# PCB-CARDLOCK.net
KiCad netlist of a schematic drawn in EAGLE
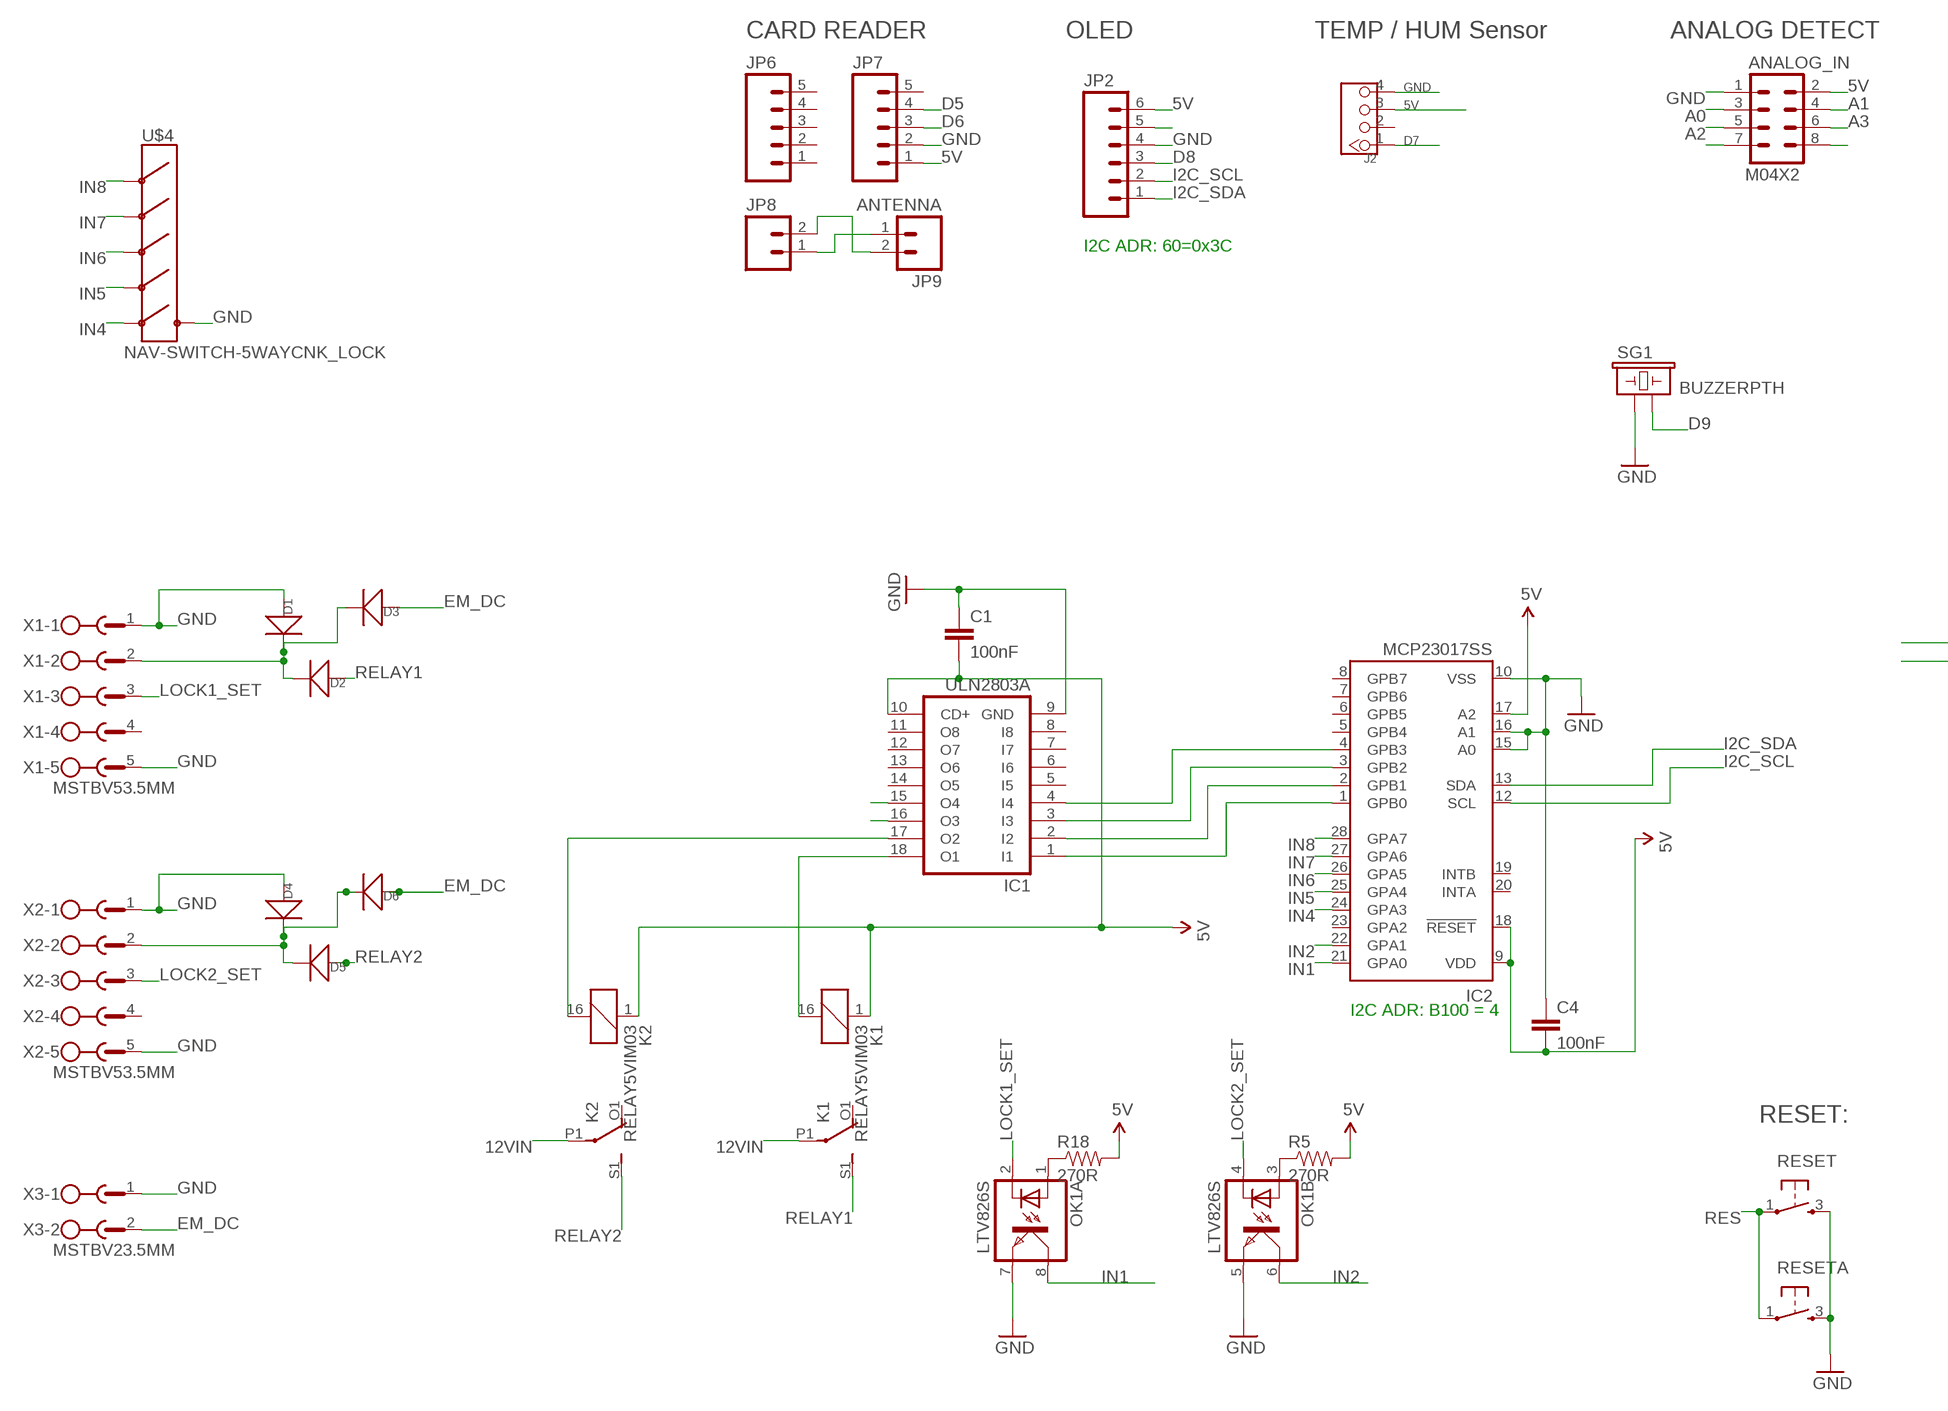
[diagram p0: schematic, sheet 1, part 1 of 2]
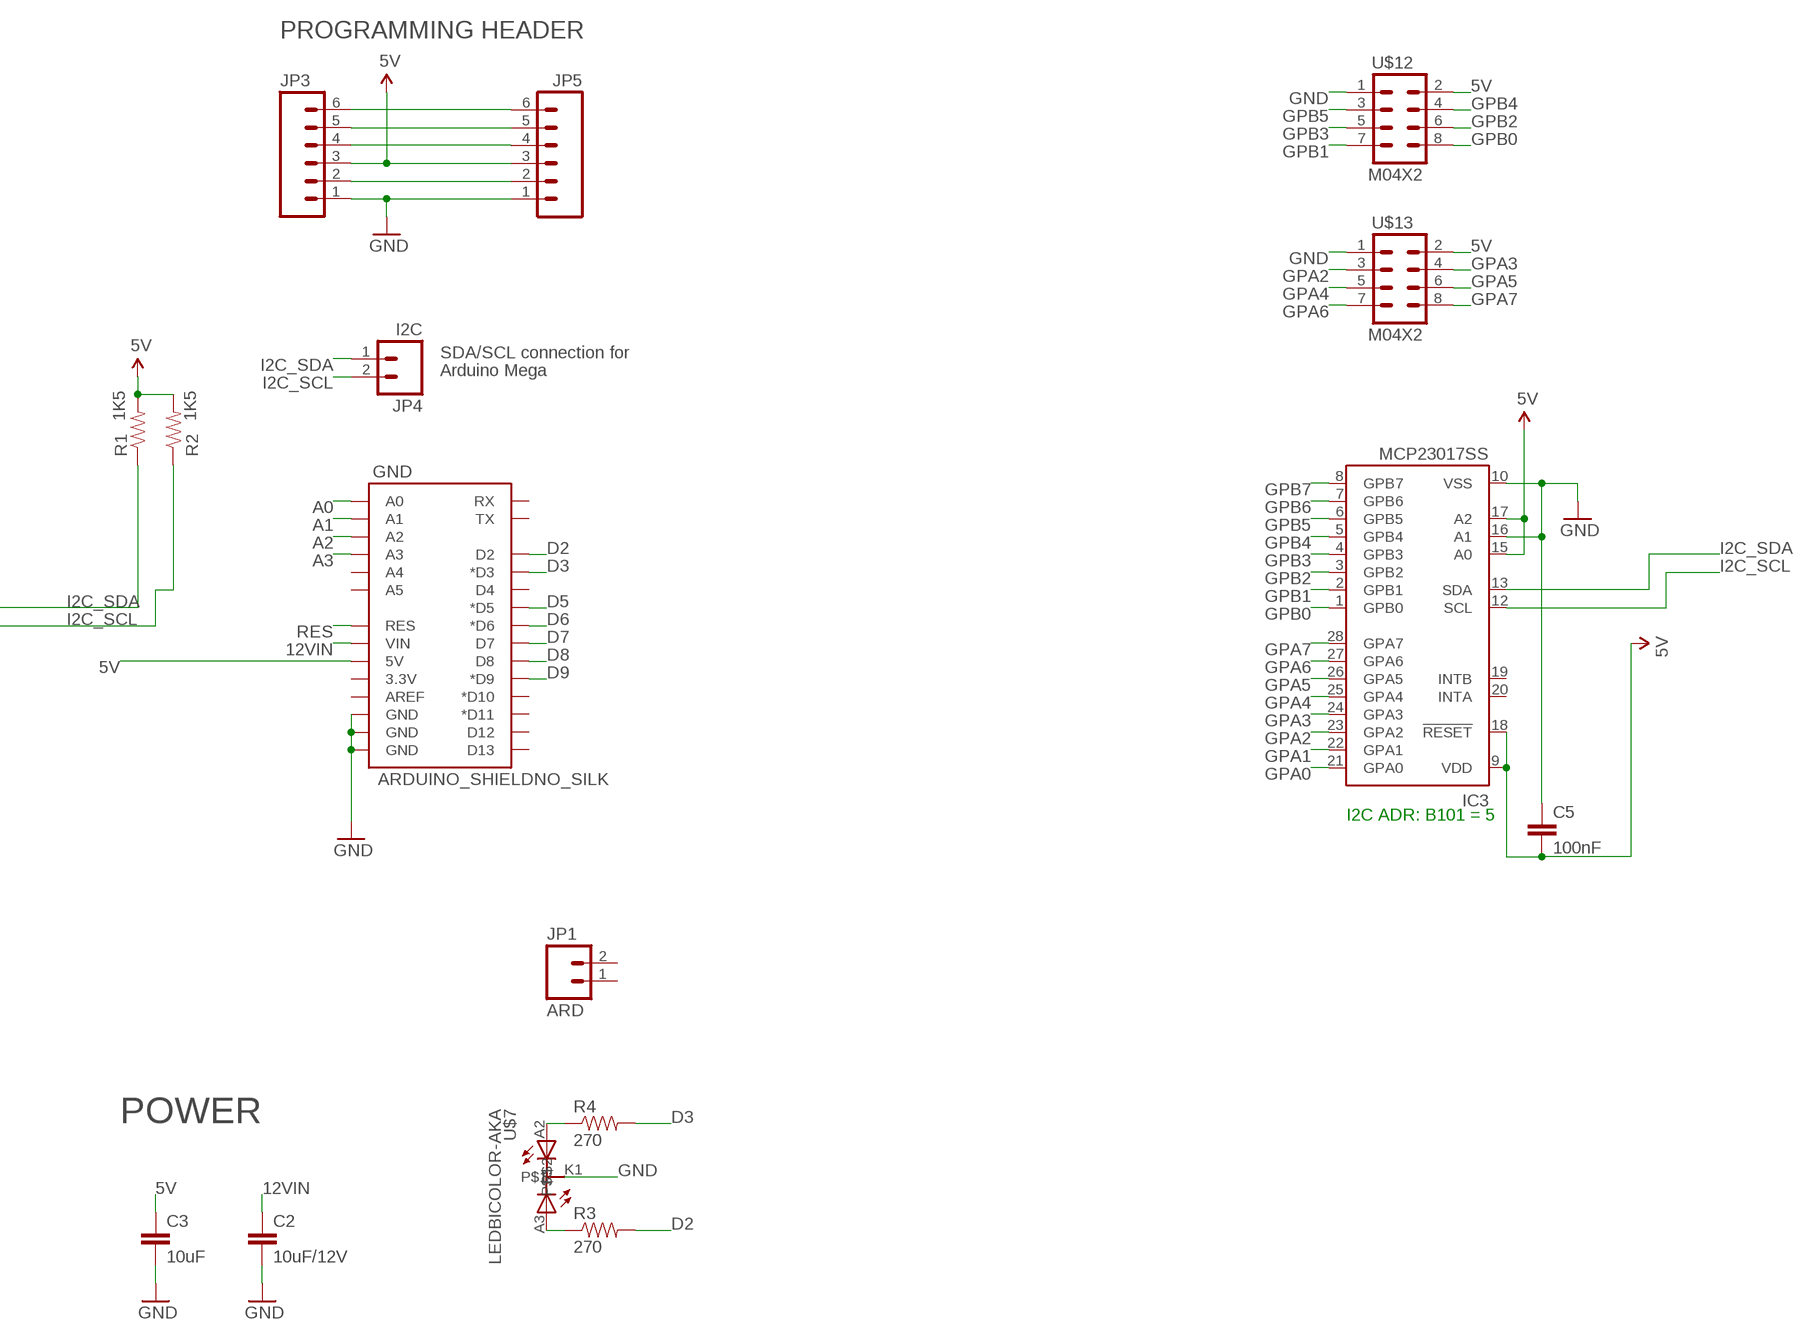
[diagram p1: schematic, sheet 1, part 2 of 2]

(export (version "E")
  (design (tool "Eeschema 10.0.6"))
  (components
    (comp (ref "ANALOG_IN")
      (value "M04X2")
      (footprint "eagle-import:2X4")
      (libsource (lib "eagle-import") (part "M04X2"))
    )
    (comp (ref "C1")
      (value "100nF")
      (footprint "eagle-import:0805")
      (libsource (lib "eagle-import") (part "CAP0805"))
    )
    (comp (ref "C2")
      (value "10uF/12V")
      (footprint "eagle-import:0805")
      (libsource (lib "eagle-import") (part "CAP0805"))
    )
    (comp (ref "C3")
      (value "10uF")
      (footprint "eagle-import:0805")
      (libsource (lib "eagle-import") (part "CAP0805"))
    )
    (comp (ref "C4")
      (value "100nF")
      (footprint "eagle-import:0603-CAP")
      (libsource (lib "eagle-import") (part "CAP0603-CAP"))
    )
    (comp (ref "C5")
      (value "100nF")
      (footprint "eagle-import:0603-CAP")
      (libsource (lib "eagle-import") (part "CAP0603-CAP"))
    )
    (comp (ref "D1")
      (value "D-SMA")
      (footprint "eagle-import:DO-214AC")
      (libsource (lib "eagle-import") (part "D-SMA"))
    )
    (comp (ref "D2")
      (value "D-SMA")
      (footprint "eagle-import:DO-214AC")
      (libsource (lib "eagle-import") (part "D-SMA"))
    )
    (comp (ref "D3")
      (value "D-SMA")
      (footprint "eagle-import:DO-214AC")
      (libsource (lib "eagle-import") (part "D-SMA"))
    )
    (comp (ref "D4")
      (value "D-SMA")
      (footprint "eagle-import:DO-214AC")
      (libsource (lib "eagle-import") (part "D-SMA"))
    )
    (comp (ref "D5")
      (value "D-SMA")
      (footprint "eagle-import:DO-214AC")
      (libsource (lib "eagle-import") (part "D-SMA"))
    )
    (comp (ref "D6")
      (value "D-SMA")
      (footprint "eagle-import:DO-214AC")
      (libsource (lib "eagle-import") (part "D-SMA"))
    )
    (comp (ref "GND")
      (value "ARDUINO_SHIELDNO_SILK")
      (footprint "eagle-import:DUEMILANOVE_VIAS")
      (libsource (lib "eagle-import") (part "ARDUINO_SHIELDNO_SILK"))
    )
    (comp (ref "IC1")
      (value "ULN2803A")
      (footprint "eagle-import:SO18W")
      (libsource (lib "eagle-import") (part "ULN2803ASO18W"))
    )
    (comp (ref "IC2")
      (value "MCP23017SS")
      (footprint "eagle-import:SSOP28")
      (fields (field (name "MF") "MICROCHIP") (field (name "MPN") "MCP23017-E/SS"))
      (libsource (lib "eagle-import") (part "MCP23017SS"))
    )
    (comp (ref "IC3")
      (value "MCP23017SS")
      (footprint "eagle-import:SSOP28")
      (fields (field (name "MF") "MICROCHIP") (field (name "MPN") "MCP23017-E/SS"))
      (libsource (lib "eagle-import") (part "MCP23017SS"))
    )
    (comp (ref "J2")
      (value "TWIG-4P-2.0-2.0")
      (footprint "eagle-import:4P-2.0")
      (libsource (lib "eagle-import") (part "TWIG-4P-2.0-2.0"))
    )
    (comp (ref "JP1")
      (value "ARD")
      (footprint "eagle-import:1X02")
      (libsource (lib "eagle-import") (part "M02PTH"))
    )
    (comp (ref "JP2")
      (value "M06POLAR")
      (footprint "eagle-import:MOLEX-1X6")
      (libsource (lib "eagle-import") (part "M06POLAR"))
    )
    (comp (ref "JP3")
      (value "M06POLAR")
      (footprint "eagle-import:MOLEX-1X6")
      (libsource (lib "eagle-import") (part "M06POLAR"))
    )
    (comp (ref "JP4")
      (value "I2C")
      (footprint "eagle-import:1X02")
      (libsource (lib "eagle-import") (part "M02PTH"))
    )
    (comp (ref "JP5")
      (value "M06POLAR")
      (footprint "eagle-import:MOLEX-1X6")
      (libsource (lib "eagle-import") (part "M06POLAR"))
    )
    (comp (ref "JP6")
      (value "M05PTH")
      (footprint "eagle-import:1X05")
      (libsource (lib "eagle-import") (part "M05PTH"))
    )
    (comp (ref "JP7")
      (value "M05PTH")
      (footprint "eagle-import:1X05")
      (libsource (lib "eagle-import") (part "M05PTH"))
    )
    (comp (ref "JP8")
      (value "M02PTH")
      (footprint "eagle-import:1X02")
      (libsource (lib "eagle-import") (part "M02PTH"))
    )
    (comp (ref "JP9")
      (value "ANTENNA")
      (footprint "eagle-import:1X02")
      (libsource (lib "eagle-import") (part "M02PTH"))
    )
    (comp (ref "K1")
      (value "RELAY5VIM03")
      (footprint "eagle-import:DS2Y")
      (libsource (lib "eagle-import") (part "RELAY5VIM03"))
    )
    (comp (ref "K2")
      (value "RELAY5VIM03")
      (footprint "eagle-import:DS2Y")
      (libsource (lib "eagle-import") (part "RELAY5VIM03"))
    )
    (comp (ref "OK1")
      (value "LTV826S")
      (footprint "eagle-import:DIL8-SMD")
      (libsource (lib "eagle-import") (part "LTV826S"))
    )
    (comp (ref "R1")
      (value "1K5")
      (footprint "eagle-import:0603-RES")
      (libsource (lib "eagle-import") (part "RESISTOR0603-RES"))
    )
    (comp (ref "R2")
      (value "1K5")
      (footprint "eagle-import:0603-RES")
      (libsource (lib "eagle-import") (part "RESISTOR0603-RES"))
    )
    (comp (ref "R3")
      (value "270")
      (footprint "eagle-import:0603-RES")
      (libsource (lib "eagle-import") (part "RESISTOR0603-RES"))
    )
    (comp (ref "R4")
      (value "270")
      (footprint "eagle-import:0603-RES")
      (libsource (lib "eagle-import") (part "RESISTOR0603-RES"))
    )
    (comp (ref "R5")
      (value "270R")
      (footprint "eagle-import:0603-RES")
      (libsource (lib "eagle-import") (part "RESISTOR0603-RES"))
    )
    (comp (ref "R18")
      (value "270R")
      (footprint "eagle-import:0603-RES")
      (libsource (lib "eagle-import") (part "RESISTOR0603-RES"))
    )
    (comp (ref "RESET")
      (value "TAC_SWITCH")
      (footprint "eagle-import:PUSHBUTTON")
      (libsource (lib "eagle-import") (part "TAC_SWITCH"))
    )
    (comp (ref "RESETA")
      (value "TAC_SWITCH")
      (footprint "eagle-import:PUSHBUTTON")
      (libsource (lib "eagle-import") (part "TAC_SWITCH"))
    )
    (comp (ref "SG1")
      (value "BUZZERPTH")
      (footprint "eagle-import:BUZZER-12MM")
      (libsource (lib "eagle-import") (part "BUZZERPTH"))
    )
    (comp (ref "U$4")
      (value "NAV-SWITCH-5WAYCNK_LOCK")
      (footprint "eagle-import:NAV-SWITCH-5WAY")
      (libsource (lib "eagle-import") (part "NAV-SWITCH-5WAYCNK_LOCK"))
    )
    (comp (ref "U$7")
      (value "LEDBICOLOR-AKA")
      (footprint "eagle-import:LED5MM-BICOLOR")
      (libsource (lib "eagle-import") (part "LEDBICOLOR-AKA"))
    )
    (comp (ref "U$12")
      (value "M04X2")
      (footprint "eagle-import:2X4")
      (libsource (lib "eagle-import") (part "M04X2"))
    )
    (comp (ref "U$13")
      (value "M04X2")
      (footprint "eagle-import:2X4")
      (libsource (lib "eagle-import") (part "M04X2"))
    )
    (comp (ref "X1")
      (value "MSTBV53.5MM")
      (footprint "eagle-import:MSTBV5-3.5")
      (libsource (lib "eagle-import") (part "MSTBV53.5MM"))
    )
    (comp (ref "X2")
      (value "MSTBV53.5MM")
      (footprint "eagle-import:MSTBV5-3.5")
      (libsource (lib "eagle-import") (part "MSTBV53.5MM"))
    )
    (comp (ref "X3")
      (value "MSTBV23.5MM")
      (footprint "eagle-import:MSTBV2-3.5")
      (libsource (lib "eagle-import") (part "MSTBV23.5MM"))
    )
  )
  (nets
    (net (code "1") (name "5V") (class "Default")
      (node (ref "ANALOG_IN") (pin "2") (pinfunction "2_2") (pintype "passive"))
      (node (ref "C1") (pin "2") (pinfunction "2_2") (pintype "passive"))
      (node (ref "C3") (pin "1") (pinfunction "1_1") (pintype "passive"))
      (node (ref "C4") (pin "2") (pinfunction "2_2") (pintype "passive"))
      (node (ref "C5") (pin "2") (pinfunction "2_2") (pintype "passive"))
      (node (ref "GND") (pin "5V") (pinfunction "5V_5V") (pintype "bidirectional"))
      (node (ref "IC1") (pin "10") (pinfunction "CD+_10") (pintype "passive"))
      (node (ref "IC2") (pin "17") (pinfunction "A2_17") (pintype "input"))
      (node (ref "IC2") (pin "18") (pinfunction "~{RESET}_18") (pintype "input"))
      (node (ref "IC2") (pin "9") (pinfunction "VDD_9") (pintype "power_in"))
      (node (ref "IC3") (pin "15") (pinfunction "A0_15") (pintype "input"))
      (node (ref "IC3") (pin "17") (pinfunction "A2_17") (pintype "input"))
      (node (ref "IC3") (pin "18") (pinfunction "~{RESET}_18") (pintype "input"))
      (node (ref "IC3") (pin "9") (pinfunction "VDD_9") (pintype "power_in"))
      (node (ref "J2") (pin "3") (pinfunction "3_3") (pintype "bidirectional"))
      (node (ref "JP2") (pin "6") (pinfunction "6_6") (pintype "passive"))
      (node (ref "JP3") (pin "3") (pinfunction "3_3") (pintype "passive"))
      (node (ref "JP5") (pin "3") (pinfunction "3_3") (pintype "passive"))
      (node (ref "JP7") (pin "1") (pinfunction "1_1") (pintype "passive"))
      (node (ref "K1") (pin "1") (pinfunction "1_1") (pintype "passive"))
      (node (ref "K2") (pin "1") (pinfunction "1_1") (pintype "passive"))
      (node (ref "R1") (pin "2") (pinfunction "2_2") (pintype "passive"))
      (node (ref "R18") (pin "2") (pinfunction "2_2") (pintype "passive"))
      (node (ref "R2") (pin "2") (pinfunction "2_2") (pintype "passive"))
      (node (ref "R5") (pin "2") (pinfunction "2_2") (pintype "passive"))
      (node (ref "U$12") (pin "2") (pinfunction "2_2") (pintype "passive"))
      (node (ref "U$13") (pin "2") (pinfunction "2_2") (pintype "passive"))
    )
    (net (code "2") (name "12VIN") (class "Default")
      (node (ref "C2") (pin "1") (pinfunction "1_1") (pintype "passive"))
      (node (ref "GND") (pin "VIN") (pinfunction "VIN_VIN") (pintype "bidirectional"))
      (node (ref "K1") (pin "P1") (pinfunction "P_P1") (pintype "passive"))
      (node (ref "K2") (pin "P1") (pinfunction "P_P1") (pintype "passive"))
    )
    (net (code "3") (name "A0") (class "Default")
      (node (ref "ANALOG_IN") (pin "3") (pinfunction "3_3") (pintype "passive"))
      (node (ref "GND") (pin "A0") (pinfunction "A0_A0") (pintype "bidirectional"))
    )
    (net (code "4") (name "A1") (class "Default")
      (node (ref "ANALOG_IN") (pin "4") (pinfunction "4_4") (pintype "passive"))
      (node (ref "GND") (pin "A1") (pinfunction "A1_A1") (pintype "bidirectional"))
    )
    (net (code "5") (name "A2") (class "Default")
      (node (ref "ANALOG_IN") (pin "5") (pinfunction "5_5") (pintype "passive"))
      (node (ref "GND") (pin "A2") (pinfunction "A2_A2") (pintype "bidirectional"))
    )
    (net (code "6") (name "A3") (class "Default")
      (node (ref "ANALOG_IN") (pin "6") (pinfunction "6_6") (pintype "passive"))
      (node (ref "GND") (pin "A3") (pinfunction "A3_A3") (pintype "bidirectional"))
    )
    (net (code "7") (name "D2") (class "Default")
      (node (ref "GND") (pin "D2") (pinfunction "D2_D2") (pintype "bidirectional"))
      (node (ref "R3") (pin "2") (pinfunction "2_2") (pintype "passive"))
    )
    (net (code "8") (name "D3") (class "Default")
      (node (ref "GND") (pin "D3") (pinfunction "*D3_D3") (pintype "bidirectional"))
      (node (ref "R4") (pin "2") (pinfunction "2_2") (pintype "passive"))
    )
    (net (code "9") (name "D5") (class "Default")
      (node (ref "GND") (pin "D5") (pinfunction "*D5_D5") (pintype "bidirectional"))
      (node (ref "JP7") (pin "4") (pinfunction "4_4") (pintype "passive"))
    )
    (net (code "10") (name "D6") (class "Default")
      (node (ref "GND") (pin "D6") (pinfunction "*D6_D6") (pintype "bidirectional"))
      (node (ref "JP7") (pin "3") (pinfunction "3_3") (pintype "passive"))
    )
    (net (code "11") (name "D7") (class "Default")
      (node (ref "GND") (pin "D7") (pinfunction "D7_D7") (pintype "bidirectional"))
      (node (ref "J2") (pin "1") (pinfunction "1_1") (pintype "bidirectional"))
    )
    (net (code "12") (name "D8") (class "Default")
      (node (ref "GND") (pin "D8") (pinfunction "D8_D8") (pintype "bidirectional"))
      (node (ref "JP2") (pin "3") (pinfunction "3_3") (pintype "passive"))
    )
    (net (code "13") (name "D9") (class "Default")
      (node (ref "GND") (pin "D9") (pinfunction "*D9_D9") (pintype "bidirectional"))
      (node (ref "SG1") (pin "-") (pinfunction "2_-") (pintype "passive"))
    )
    (net (code "14") (name "EM_DC") (class "Default")
      (node (ref "D3") (pin "1") (pinfunction "+_1") (pintype "passive"))
      (node (ref "D6") (pin "1") (pinfunction "+_1") (pintype "passive"))
      (node (ref "X3") (pin "2") (pinfunction "1_2") (pintype "passive"))
    )
    (net (code "15") (name "GND") (class "Default")
      (node (ref "ANALOG_IN") (pin "1") (pinfunction "1_1") (pintype "passive"))
      (node (ref "C1") (pin "1") (pinfunction "1_1") (pintype "passive"))
      (node (ref "C2") (pin "2") (pinfunction "2_2") (pintype "passive"))
      (node (ref "C3") (pin "2") (pinfunction "2_2") (pintype "passive"))
      (node (ref "C4") (pin "1") (pinfunction "1_1") (pintype "passive"))
      (node (ref "C5") (pin "1") (pinfunction "1_1") (pintype "passive"))
      (node (ref "D1") (pin "1") (pinfunction "+_1") (pintype "passive"))
      (node (ref "D4") (pin "1") (pinfunction "+_1") (pintype "passive"))
      (node (ref "GND") (pin "GND@0") (pinfunction "GND_GND@0") (pintype "bidirectional"))
      (node (ref "GND") (pin "GND@1") (pinfunction "GND_GND@1") (pintype "bidirectional"))
      (node (ref "GND") (pin "GND@2") (pinfunction "GND_GND@2") (pintype "bidirectional"))
      (node (ref "IC1") (pin "9") (pinfunction "GND_9") (pintype "power_in"))
      (node (ref "IC2") (pin "10") (pinfunction "VSS_10") (pintype "power_in"))
      (node (ref "IC2") (pin "15") (pinfunction "A0_15") (pintype "input"))
      (node (ref "IC2") (pin "16") (pinfunction "A1_16") (pintype "input"))
      (node (ref "IC3") (pin "10") (pinfunction "VSS_10") (pintype "power_in"))
      (node (ref "IC3") (pin "16") (pinfunction "A1_16") (pintype "input"))
      (node (ref "J2") (pin "4") (pinfunction "4_4") (pintype "bidirectional"))
      (node (ref "JP2") (pin "4") (pinfunction "4_4") (pintype "passive"))
      (node (ref "JP3") (pin "1") (pinfunction "1_1") (pintype "passive"))
      (node (ref "JP5") (pin "1") (pinfunction "1_1") (pintype "passive"))
      (node (ref "JP7") (pin "2") (pinfunction "2_2") (pintype "passive"))
      (node (ref "OK1") (pin "5") (pinfunction "EMIT_5") (pintype "passive"))
      (node (ref "OK1") (pin "7") (pinfunction "EMIT_7") (pintype "passive"))
      (node (ref "RESET") (pin "3") (pinfunction "3_3") (pintype "passive"))
      (node (ref "RESETA") (pin "3") (pinfunction "3_3") (pintype "passive"))
      (node (ref "SG1") (pin "+") (pinfunction "1_+") (pintype "passive"))
      (node (ref "U$12") (pin "1") (pinfunction "1_1") (pintype "passive"))
      (node (ref "U$13") (pin "1") (pinfunction "1_1") (pintype "passive"))
      (node (ref "U$4") (pin "PIN4") (pinfunction "COMMON_PIN4") (pintype "bidirectional"))
      (node (ref "U$7") (pin "K1") (pinfunction "P$1_K1") (pintype "bidirectional"))
      (node (ref "X1") (pin "1") (pinfunction "1_1") (pintype "passive"))
      (node (ref "X1") (pin "5") (pinfunction "1_5") (pintype "passive"))
      (node (ref "X2") (pin "1") (pinfunction "1_1") (pintype "passive"))
      (node (ref "X2") (pin "5") (pinfunction "1_5") (pintype "passive"))
      (node (ref "X3") (pin "1") (pinfunction "1_1") (pintype "passive"))
    )
    (net (code "16") (name "GPA0") (class "Default")
      (node (ref "IC3") (pin "21") (pinfunction "GPA0_21") (pintype "bidirectional"))
    )
    (net (code "17") (name "GPA1") (class "Default")
      (node (ref "IC3") (pin "22") (pinfunction "GPA1_22") (pintype "bidirectional"))
    )
    (net (code "18") (name "GPA2") (class "Default")
      (node (ref "IC3") (pin "23") (pinfunction "GPA2_23") (pintype "bidirectional"))
      (node (ref "U$13") (pin "3") (pinfunction "3_3") (pintype "passive"))
    )
    (net (code "19") (name "GPA3") (class "Default")
      (node (ref "IC3") (pin "24") (pinfunction "GPA3_24") (pintype "bidirectional"))
      (node (ref "U$13") (pin "4") (pinfunction "4_4") (pintype "passive"))
    )
    (net (code "20") (name "GPA4") (class "Default")
      (node (ref "IC3") (pin "25") (pinfunction "GPA4_25") (pintype "bidirectional"))
      (node (ref "U$13") (pin "5") (pinfunction "5_5") (pintype "passive"))
    )
    (net (code "21") (name "GPA5") (class "Default")
      (node (ref "IC3") (pin "26") (pinfunction "GPA5_26") (pintype "bidirectional"))
      (node (ref "U$13") (pin "6") (pinfunction "6_6") (pintype "passive"))
    )
    (net (code "22") (name "GPA6") (class "Default")
      (node (ref "IC3") (pin "27") (pinfunction "GPA6_27") (pintype "bidirectional"))
      (node (ref "U$13") (pin "7") (pinfunction "7_7") (pintype "passive"))
    )
    (net (code "23") (name "GPA7") (class "Default")
      (node (ref "IC3") (pin "28") (pinfunction "GPA7_28") (pintype "bidirectional"))
      (node (ref "U$13") (pin "8") (pinfunction "8_8") (pintype "passive"))
    )
    (net (code "24") (name "GPB0") (class "Default")
      (node (ref "IC3") (pin "1") (pinfunction "GPB0_1") (pintype "bidirectional"))
      (node (ref "U$12") (pin "8") (pinfunction "8_8") (pintype "passive"))
    )
    (net (code "25") (name "GPB1") (class "Default")
      (node (ref "IC3") (pin "2") (pinfunction "GPB1_2") (pintype "bidirectional"))
      (node (ref "U$12") (pin "7") (pinfunction "7_7") (pintype "passive"))
    )
    (net (code "26") (name "GPB2") (class "Default")
      (node (ref "IC3") (pin "3") (pinfunction "GPB2_3") (pintype "bidirectional"))
      (node (ref "U$12") (pin "6") (pinfunction "6_6") (pintype "passive"))
    )
    (net (code "27") (name "GPB3") (class "Default")
      (node (ref "IC3") (pin "4") (pinfunction "GPB3_4") (pintype "bidirectional"))
      (node (ref "U$12") (pin "5") (pinfunction "5_5") (pintype "passive"))
    )
    (net (code "28") (name "GPB4") (class "Default")
      (node (ref "IC3") (pin "5") (pinfunction "GPB4_5") (pintype "bidirectional"))
      (node (ref "U$12") (pin "4") (pinfunction "4_4") (pintype "passive"))
    )
    (net (code "29") (name "GPB5") (class "Default")
      (node (ref "IC3") (pin "6") (pinfunction "GPB5_6") (pintype "bidirectional"))
      (node (ref "U$12") (pin "3") (pinfunction "3_3") (pintype "passive"))
    )
    (net (code "30") (name "GPB6") (class "Default")
      (node (ref "IC3") (pin "7") (pinfunction "GPB6_7") (pintype "bidirectional"))
    )
    (net (code "31") (name "GPB7") (class "Default")
      (node (ref "IC3") (pin "8") (pinfunction "GPB7_8") (pintype "bidirectional"))
    )
    (net (code "32") (name "I2C_SCL") (class "Default")
      (node (ref "IC2") (pin "12") (pinfunction "SCL_12") (pintype "input"))
      (node (ref "IC3") (pin "12") (pinfunction "SCL_12") (pintype "input"))
      (node (ref "JP2") (pin "2") (pinfunction "2_2") (pintype "passive"))
      (node (ref "JP4") (pin "2") (pinfunction "2_2") (pintype "passive"))
      (node (ref "R2") (pin "1") (pinfunction "1_1") (pintype "passive"))
    )
    (net (code "33") (name "I2C_SDA") (class "Default")
      (node (ref "IC2") (pin "13") (pinfunction "SDA_13") (pintype "bidirectional"))
      (node (ref "IC3") (pin "13") (pinfunction "SDA_13") (pintype "bidirectional"))
      (node (ref "JP2") (pin "1") (pinfunction "1_1") (pintype "passive"))
      (node (ref "JP4") (pin "1") (pinfunction "1_1") (pintype "passive"))
      (node (ref "R1") (pin "1") (pinfunction "1_1") (pintype "passive"))
    )
    (net (code "34") (name "IN1") (class "Default")
      (node (ref "IC2") (pin "21") (pinfunction "GPA0_21") (pintype "bidirectional"))
      (node (ref "OK1") (pin "8") (pinfunction "COL_8") (pintype "passive"))
    )
    (net (code "35") (name "IN2") (class "Default")
      (node (ref "IC2") (pin "22") (pinfunction "GPA1_22") (pintype "bidirectional"))
      (node (ref "OK1") (pin "6") (pinfunction "COL_6") (pintype "passive"))
    )
    (net (code "36") (name "IN4") (class "Default")
      (node (ref "IC2") (pin "24") (pinfunction "GPA3_24") (pintype "bidirectional"))
      (node (ref "U$4") (pin "PIN6") (pinfunction "PUSH_PIN6") (pintype "bidirectional"))
    )
    (net (code "37") (name "IN5") (class "Default")
      (node (ref "IC2") (pin "25") (pinfunction "GPA4_25") (pintype "bidirectional"))
      (node (ref "U$4") (pin "PIN5") (pinfunction "RIGHT_PIN5") (pintype "bidirectional"))
    )
    (net (code "38") (name "IN6") (class "Default")
      (node (ref "IC2") (pin "26") (pinfunction "GPA5_26") (pintype "bidirectional"))
      (node (ref "U$4") (pin "PIN2") (pinfunction "LEFT_PIN2") (pintype "bidirectional"))
    )
    (net (code "39") (name "IN7") (class "Default")
      (node (ref "IC2") (pin "27") (pinfunction "GPA6_27") (pintype "bidirectional"))
      (node (ref "U$4") (pin "PIN3") (pinfunction "DWN_PIN3") (pintype "bidirectional"))
    )
    (net (code "40") (name "IN8") (class "Default")
      (node (ref "IC2") (pin "28") (pinfunction "GPA7_28") (pintype "bidirectional"))
      (node (ref "U$4") (pin "PIN1") (pinfunction "UP_PIN1") (pintype "bidirectional"))
    )
    (net (code "41") (name "LOCK1_SET") (class "Default")
      (node (ref "OK1") (pin "2") (pinfunction "C_2") (pintype "passive"))
      (node (ref "X1") (pin "3") (pinfunction "1_3") (pintype "passive"))
    )
    (net (code "42") (name "LOCK2_SET") (class "Default")
      (node (ref "OK1") (pin "4") (pinfunction "C_4") (pintype "passive"))
      (node (ref "X2") (pin "3") (pinfunction "1_3") (pintype "passive"))
    )
    (net (code "43") (name "Net-(D1--)") (class "Default")
      (node (ref "D1") (pin "2") (pinfunction "-_2") (pintype "passive"))
      (node (ref "D2") (pin "2") (pinfunction "-_2") (pintype "passive"))
      (node (ref "D3") (pin "2") (pinfunction "-_2") (pintype "passive"))
      (node (ref "X1") (pin "2") (pinfunction "1_2") (pintype "passive"))
    )
    (net (code "44") (name "Net-(D4--)") (class "Default")
      (node (ref "D4") (pin "2") (pinfunction "-_2") (pintype "passive"))
      (node (ref "D5") (pin "2") (pinfunction "-_2") (pintype "passive"))
      (node (ref "D6") (pin "2") (pinfunction "-_2") (pintype "passive"))
      (node (ref "X2") (pin "2") (pinfunction "1_2") (pintype "passive"))
    )
    (net (code "45") (name "Net-(IC1-I1)") (class "Default")
      (node (ref "IC1") (pin "1") (pinfunction "I1_1") (pintype "input"))
      (node (ref "IC2") (pin "1") (pinfunction "GPB0_1") (pintype "bidirectional"))
    )
    (net (code "46") (name "Net-(IC1-I2)") (class "Default")
      (node (ref "IC1") (pin "2") (pinfunction "I2_2") (pintype "input"))
      (node (ref "IC2") (pin "2") (pinfunction "GPB1_2") (pintype "bidirectional"))
    )
    (net (code "47") (name "Net-(IC1-I3)") (class "Default")
      (node (ref "IC1") (pin "3") (pinfunction "I3_3") (pintype "input"))
      (node (ref "IC2") (pin "3") (pinfunction "GPB2_3") (pintype "bidirectional"))
    )
    (net (code "48") (name "Net-(IC1-I4)") (class "Default")
      (node (ref "IC1") (pin "4") (pinfunction "I4_4") (pintype "input"))
      (node (ref "IC2") (pin "4") (pinfunction "GPB3_4") (pintype "bidirectional"))
    )
    (net (code "49") (name "Net-(IC1-O1)") (class "Default")
      (node (ref "IC1") (pin "18") (pinfunction "O1_18") (pintype "open_collector"))
      (node (ref "K1") (pin "16") (pinfunction "2_16") (pintype "passive"))
    )
    (net (code "50") (name "Net-(IC1-O2)") (class "Default")
      (node (ref "IC1") (pin "17") (pinfunction "O2_17") (pintype "open_collector"))
      (node (ref "K2") (pin "16") (pinfunction "2_16") (pintype "passive"))
    )
    (net (code "51") (name "Net-(JP3-Pad2)") (class "Default")
      (node (ref "JP3") (pin "2") (pinfunction "2_2") (pintype "passive"))
      (node (ref "JP5") (pin "2") (pinfunction "2_2") (pintype "passive"))
    )
    (net (code "52") (name "Net-(JP3-Pad4)") (class "Default")
      (node (ref "JP3") (pin "4") (pinfunction "4_4") (pintype "passive"))
      (node (ref "JP5") (pin "4") (pinfunction "4_4") (pintype "passive"))
    )
    (net (code "53") (name "Net-(JP3-Pad5)") (class "Default")
      (node (ref "JP3") (pin "5") (pinfunction "5_5") (pintype "passive"))
      (node (ref "JP5") (pin "5") (pinfunction "5_5") (pintype "passive"))
    )
    (net (code "54") (name "Net-(JP3-Pad6)") (class "Default")
      (node (ref "JP3") (pin "6") (pinfunction "6_6") (pintype "passive"))
      (node (ref "JP5") (pin "6") (pinfunction "6_6") (pintype "passive"))
    )
    (net (code "55") (name "Net-(JP8-Pad1)") (class "Default")
      (node (ref "JP8") (pin "1") (pinfunction "1_1") (pintype "passive"))
      (node (ref "JP9") (pin "1") (pinfunction "1_1") (pintype "passive"))
    )
    (net (code "56") (name "Net-(JP8-Pad2)") (class "Default")
      (node (ref "JP8") (pin "2") (pinfunction "2_2") (pintype "passive"))
      (node (ref "JP9") (pin "2") (pinfunction "2_2") (pintype "passive"))
    )
    (net (code "57") (name "Net-(OK1A-A)") (class "Default")
      (node (ref "OK1") (pin "1") (pinfunction "A_1") (pintype "passive"))
      (node (ref "R18") (pin "1") (pinfunction "1_1") (pintype "passive"))
    )
    (net (code "58") (name "Net-(OK1B-A)") (class "Default")
      (node (ref "OK1") (pin "3") (pinfunction "A_3") (pintype "passive"))
      (node (ref "R5") (pin "1") (pinfunction "1_1") (pintype "passive"))
    )
    (net (code "59") (name "Net-(U$7-P$2)") (class "Default")
      (node (ref "R4") (pin "1") (pinfunction "1_1") (pintype "passive"))
      (node (ref "U$7") (pin "A2") (pinfunction "P$2_A2") (pintype "bidirectional"))
    )
    (net (code "60") (name "Net-(U$7-P$3)") (class "Default")
      (node (ref "R3") (pin "1") (pinfunction "1_1") (pintype "passive"))
      (node (ref "U$7") (pin "A3") (pinfunction "P$3_A3") (pintype "bidirectional"))
    )
    (net (code "61") (name "RELAY1") (class "Default")
      (node (ref "D2") (pin "1") (pinfunction "+_1") (pintype "passive"))
      (node (ref "K1") (pin "S1") (pinfunction "S_S1") (pintype "passive"))
    )
    (net (code "62") (name "RELAY2") (class "Default")
      (node (ref "D5") (pin "1") (pinfunction "+_1") (pintype "passive"))
      (node (ref "K2") (pin "S1") (pinfunction "S_S1") (pintype "passive"))
    )
    (net (code "63") (name "RES") (class "Default")
      (node (ref "GND") (pin "RES") (pinfunction "RES_RES") (pintype "bidirectional"))
      (node (ref "RESET") (pin "1") (pinfunction "1_1") (pintype "passive"))
      (node (ref "RESETA") (pin "1") (pinfunction "1_1") (pintype "passive"))
    )
    (net (code "64") (name "unconnected-(ANALOG_IN-Pad7)") (class "Default")
      (node (ref "ANALOG_IN") (pin "7") (pinfunction "7_7") (pintype "passive"))
    )
    (net (code "65") (name "unconnected-(ANALOG_IN-Pad8)") (class "Default")
      (node (ref "ANALOG_IN") (pin "8") (pinfunction "8_8") (pintype "passive"))
    )
    (net (code "66") (name "unconnected-(GND-*D10-PadD10)") (class "Default")
      (node (ref "GND") (pin "D10") (pinfunction "*D10_D10") (pintype "bidirectional"))
    )
    (net (code "67") (name "unconnected-(GND-*D11-PadD11)") (class "Default")
      (node (ref "GND") (pin "D11") (pinfunction "*D11_D11") (pintype "bidirectional"))
    )
    (net (code "68") (name "unconnected-(GND-Pad3.3V)") (class "Default")
      (node (ref "GND") (pin "3.3V") (pinfunction "3.3V_3.3V") (pintype "bidirectional"))
    )
    (net (code "69") (name "unconnected-(GND-PadA4)") (class "Default")
      (node (ref "GND") (pin "A4") (pinfunction "A4_A4") (pintype "bidirectional"))
    )
    (net (code "70") (name "unconnected-(GND-PadA5)") (class "Default")
      (node (ref "GND") (pin "A5") (pinfunction "A5_A5") (pintype "bidirectional"))
    )
    (net (code "71") (name "unconnected-(GND-PadAREF)") (class "Default")
      (node (ref "GND") (pin "AREF") (pinfunction "AREF_AREF") (pintype "bidirectional"))
    )
    (net (code "72") (name "unconnected-(GND-PadD4)") (class "Default")
      (node (ref "GND") (pin "D4") (pinfunction "D4_D4") (pintype "bidirectional"))
    )
    (net (code "73") (name "unconnected-(GND-PadD12)") (class "Default")
      (node (ref "GND") (pin "D12") (pinfunction "D12_D12") (pintype "bidirectional"))
    )
    (net (code "74") (name "unconnected-(GND-PadD13)") (class "Default")
      (node (ref "GND") (pin "D13") (pinfunction "D13_D13") (pintype "bidirectional"))
    )
    (net (code "75") (name "unconnected-(GND-PadRX)") (class "Default")
      (node (ref "GND") (pin "RX") (pinfunction "RX_RX") (pintype "bidirectional"))
    )
    (net (code "76") (name "unconnected-(GND-PadTX)") (class "Default")
      (node (ref "GND") (pin "TX") (pinfunction "TX_TX") (pintype "bidirectional"))
    )
    (net (code "77") (name "unconnected-(IC1-I5-Pad5)") (class "Default")
      (node (ref "IC1") (pin "5") (pinfunction "I5_5") (pintype "input"))
    )
    (net (code "78") (name "unconnected-(IC1-I6-Pad6)") (class "Default")
      (node (ref "IC1") (pin "6") (pinfunction "I6_6") (pintype "input"))
    )
    (net (code "79") (name "unconnected-(IC1-I7-Pad7)") (class "Default")
      (node (ref "IC1") (pin "7") (pinfunction "I7_7") (pintype "input"))
    )
    (net (code "80") (name "unconnected-(IC1-I8-Pad8)") (class "Default")
      (node (ref "IC1") (pin "8") (pinfunction "I8_8") (pintype "input"))
    )
    (net (code "81") (name "unconnected-(IC1-O3-Pad16)") (class "Default")
      (node (ref "IC1") (pin "16") (pinfunction "O3_16") (pintype "open_collector"))
    )
    (net (code "82") (name "unconnected-(IC1-O4-Pad15)") (class "Default")
      (node (ref "IC1") (pin "15") (pinfunction "O4_15") (pintype "open_collector"))
    )
    (net (code "83") (name "unconnected-(IC1-O5-Pad14)") (class "Default")
      (node (ref "IC1") (pin "14") (pinfunction "O5_14") (pintype "open_collector"))
    )
    (net (code "84") (name "unconnected-(IC1-O6-Pad13)") (class "Default")
      (node (ref "IC1") (pin "13") (pinfunction "O6_13") (pintype "open_collector"))
    )
    (net (code "85") (name "unconnected-(IC1-O7-Pad12)") (class "Default")
      (node (ref "IC1") (pin "12") (pinfunction "O7_12") (pintype "open_collector"))
    )
    (net (code "86") (name "unconnected-(IC1-O8-Pad11)") (class "Default")
      (node (ref "IC1") (pin "11") (pinfunction "O8_11") (pintype "open_collector"))
    )
    (net (code "87") (name "unconnected-(IC2-GPA2-Pad23)") (class "Default")
      (node (ref "IC2") (pin "23") (pinfunction "GPA2_23") (pintype "bidirectional"))
    )
    (net (code "88") (name "unconnected-(IC2-GPB4-Pad5)") (class "Default")
      (node (ref "IC2") (pin "5") (pinfunction "GPB4_5") (pintype "bidirectional"))
    )
    (net (code "89") (name "unconnected-(IC2-GPB5-Pad6)") (class "Default")
      (node (ref "IC2") (pin "6") (pinfunction "GPB5_6") (pintype "bidirectional"))
    )
    (net (code "90") (name "unconnected-(IC2-GPB6-Pad7)") (class "Default")
      (node (ref "IC2") (pin "7") (pinfunction "GPB6_7") (pintype "bidirectional"))
    )
    (net (code "91") (name "unconnected-(IC2-GPB7-Pad8)") (class "Default")
      (node (ref "IC2") (pin "8") (pinfunction "GPB7_8") (pintype "bidirectional"))
    )
    (net (code "92") (name "unconnected-(IC2-INTA-Pad20)") (class "Default")
      (node (ref "IC2") (pin "20") (pinfunction "INTA_20") (pintype "output"))
    )
    (net (code "93") (name "unconnected-(IC2-INTB-Pad19)") (class "Default")
      (node (ref "IC2") (pin "19") (pinfunction "INTB_19") (pintype "output"))
    )
    (net (code "94") (name "unconnected-(IC3-INTA-Pad20)") (class "Default")
      (node (ref "IC3") (pin "20") (pinfunction "INTA_20") (pintype "output"))
    )
    (net (code "95") (name "unconnected-(IC3-INTB-Pad19)") (class "Default")
      (node (ref "IC3") (pin "19") (pinfunction "INTB_19") (pintype "output"))
    )
    (net (code "96") (name "unconnected-(J2-Pad2)") (class "Default")
      (node (ref "J2") (pin "2") (pinfunction "2_2") (pintype "bidirectional"))
    )
    (net (code "97") (name "unconnected-(JP1-Pad1)") (class "Default")
      (node (ref "JP1") (pin "1") (pinfunction "1_1") (pintype "passive"))
    )
    (net (code "98") (name "unconnected-(JP1-Pad2)") (class "Default")
      (node (ref "JP1") (pin "2") (pinfunction "2_2") (pintype "passive"))
    )
    (net (code "99") (name "unconnected-(JP2-Pad5)") (class "Default")
      (node (ref "JP2") (pin "5") (pinfunction "5_5") (pintype "passive"))
    )
    (net (code "100") (name "unconnected-(JP6-Pad1)") (class "Default")
      (node (ref "JP6") (pin "1") (pinfunction "1_1") (pintype "passive"))
    )
    (net (code "101") (name "unconnected-(JP6-Pad2)") (class "Default")
      (node (ref "JP6") (pin "2") (pinfunction "2_2") (pintype "passive"))
    )
    (net (code "102") (name "unconnected-(JP6-Pad3)") (class "Default")
      (node (ref "JP6") (pin "3") (pinfunction "3_3") (pintype "passive"))
    )
    (net (code "103") (name "unconnected-(JP6-Pad4)") (class "Default")
      (node (ref "JP6") (pin "4") (pinfunction "4_4") (pintype "passive"))
    )
    (net (code "104") (name "unconnected-(JP6-Pad5)") (class "Default")
      (node (ref "JP6") (pin "5") (pinfunction "5_5") (pintype "passive"))
    )
    (net (code "105") (name "unconnected-(JP7-Pad5)") (class "Default")
      (node (ref "JP7") (pin "5") (pinfunction "5_5") (pintype "passive"))
    )
    (net (code "106") (name "unconnected-(K1B-O-PadO1)") (class "Default")
      (node (ref "K1") (pin "O1") (pinfunction "O_O1") (pintype "passive"))
    )
    (net (code "107") (name "unconnected-(K2B-O-PadO1)") (class "Default")
      (node (ref "K2") (pin "O1") (pinfunction "O_O1") (pintype "passive"))
    )
    (net (code "108") (name "unconnected-(X1D-1-Pad4)") (class "Default")
      (node (ref "X1") (pin "4") (pinfunction "1_4") (pintype "passive"))
    )
    (net (code "109") (name "unconnected-(X2D-1-Pad4)") (class "Default")
      (node (ref "X2") (pin "4") (pinfunction "1_4") (pintype "passive"))
    )
  )
)
